# Screambooth.net
KiCad netlist of a schematic drawn in EAGLE
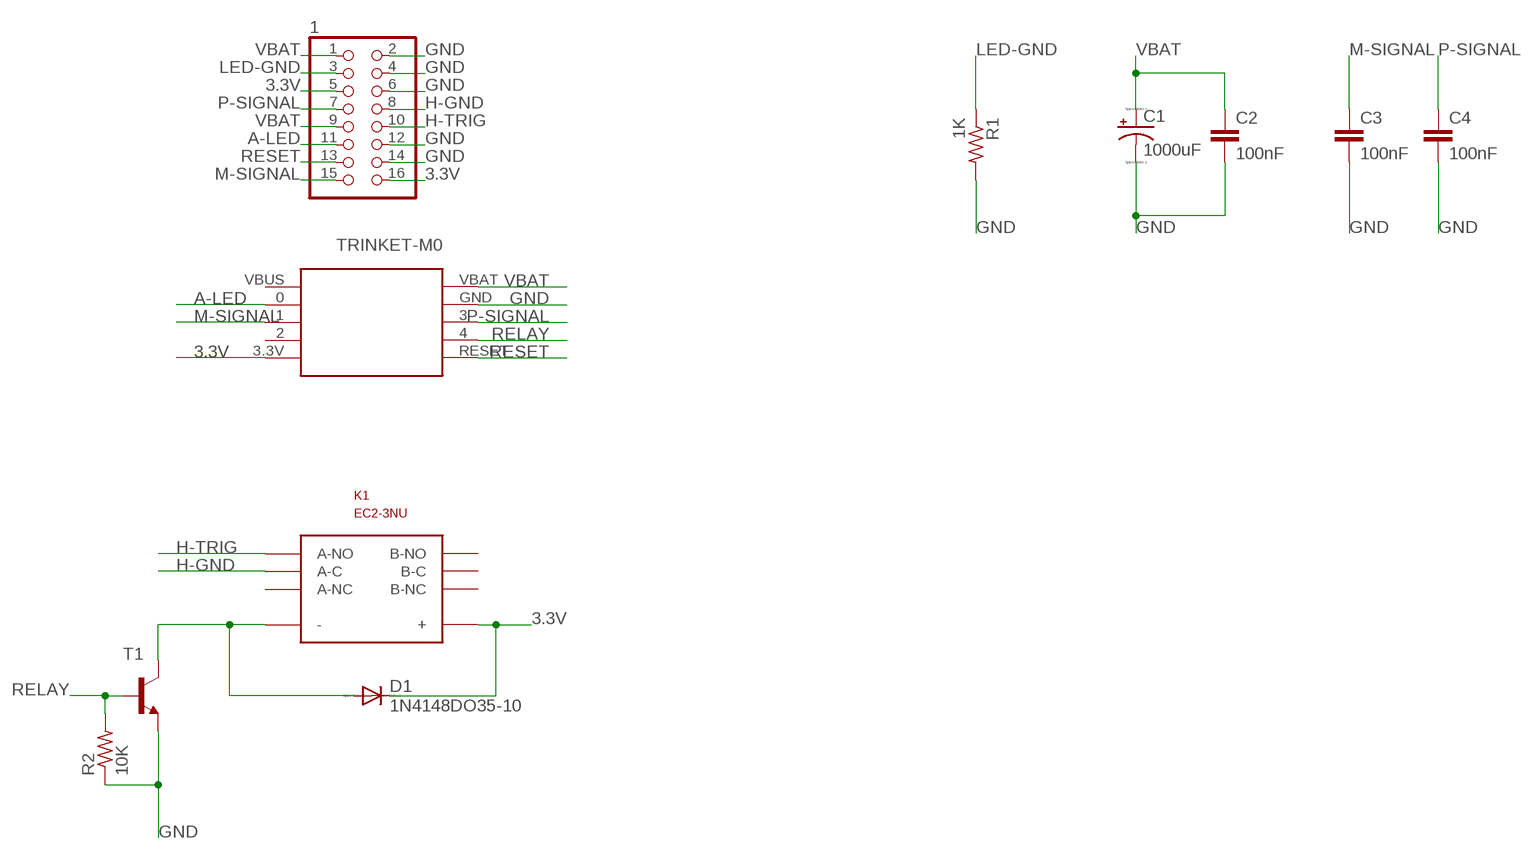
[diagram p0: schematic, sheet 1]

(export (version "E")
  (design (tool "Eeschema 10.0.6"))
  (components
    (comp (ref "1")
      (value "PINHD-2X8")
      (footprint "eagle-import:2X08")
      (libsource (lib "eagle-import") (part "PINHD-2X8"))
    )
    (comp (ref "C1")
      (value "1000uF")
      (footprint "eagle-import:E5-10,5")
      (libsource (lib "eagle-import") (part "CPOL-USE5-10.5"))
    )
    (comp (ref "C2")
      (value "100nF")
      (footprint "eagle-import:C050-030X075")
      (libsource (lib "eagle-import") (part "C-EU050-030X075"))
    )
    (comp (ref "C3")
      (value "100nF")
      (footprint "eagle-import:C050-030X075")
      (libsource (lib "eagle-import") (part "C-EU050-030X075"))
    )
    (comp (ref "C4")
      (value "100nF")
      (footprint "eagle-import:C050-030X075")
      (libsource (lib "eagle-import") (part "C-EU050-030X075"))
    )
    (comp (ref "D1")
      (value "1N4148DO35-10")
      (footprint "eagle-import:DO35-10")
      (libsource (lib "eagle-import") (part "1N4148DO35-10"))
    )
    (comp (ref "K1")
      (value "EC2-3NU")
      (footprint "eagle-import:EC2-RELAY")
      (libsource (lib "eagle-import") (part "EC2-3NU"))
    )
    (comp (ref "R1")
      (value "1K")
      (footprint "eagle-import:0207_10")
      (libsource (lib "eagle-import") (part "R-US_0207/10"))
    )
    (comp (ref "R2")
      (value "10K")
      (footprint "eagle-import:0207_10")
      (libsource (lib "eagle-import") (part "R-US_0207/10"))
    )
    (comp (ref "T1")
      (value "2N3904")
      (footprint "eagle-import:TO92")
      (libsource (lib "eagle-import") (part "2N3904"))
    )
    (comp (ref "TRINKET-M0")
      (value "TRINKET-M0")
      (footprint "eagle-import:TRINKET-M0")
      (libsource (lib "eagle-import") (part "TRINKET-M0"))
    )
  )
  (nets
    (net (code "1") (name "/3.3V") (class "Default")
      (node (ref "1") (pin "16") (pinfunction "16_16") (pintype "passive"))
      (node (ref "1") (pin "5") (pinfunction "5_5") (pintype "passive"))
      (node (ref "D1") (pin "C") (pinfunction "C_C") (pintype "passive"))
      (node (ref "K1") (pin "+") (pinfunction "+_+") (pintype "bidirectional"))
      (node (ref "TRINKET-M0") (pin "3.3V") (pinfunction "3.3V_3.3V") (pintype "bidirectional"))
    )
    (net (code "2") (name "/A-LED") (class "Default")
      (node (ref "1") (pin "11") (pinfunction "11_11") (pintype "passive"))
      (node (ref "TRINKET-M0") (pin "0") (pinfunction "0_0") (pintype "bidirectional"))
    )
    (net (code "3") (name "/GND") (class "Default")
      (node (ref "1") (pin "12") (pinfunction "12_12") (pintype "passive"))
      (node (ref "1") (pin "14") (pinfunction "14_14") (pintype "passive"))
      (node (ref "1") (pin "2") (pinfunction "2_2") (pintype "passive"))
      (node (ref "1") (pin "4") (pinfunction "4_4") (pintype "passive"))
      (node (ref "1") (pin "6") (pinfunction "6_6") (pintype "passive"))
      (node (ref "C1") (pin "-") (pinfunction "-_-") (pintype "passive"))
      (node (ref "C2") (pin "2") (pinfunction "2_2") (pintype "passive"))
      (node (ref "C3") (pin "2") (pinfunction "2_2") (pintype "passive"))
      (node (ref "C4") (pin "2") (pinfunction "2_2") (pintype "passive"))
      (node (ref "R1") (pin "2") (pinfunction "2_2") (pintype "passive"))
      (node (ref "R2") (pin "1") (pinfunction "1_1") (pintype "passive"))
      (node (ref "T1") (pin "3") (pinfunction "E_3") (pintype "passive"))
      (node (ref "TRINKET-M0") (pin "GND") (pinfunction "GND_GND") (pintype "bidirectional"))
    )
    (net (code "4") (name "/H-GND") (class "Default")
      (node (ref "1") (pin "8") (pinfunction "8_8") (pintype "passive"))
      (node (ref "K1") (pin "A-C") (pinfunction "A-C_A-C") (pintype "bidirectional"))
    )
    (net (code "5") (name "/H-TRIG") (class "Default")
      (node (ref "1") (pin "10") (pinfunction "10_10") (pintype "passive"))
      (node (ref "K1") (pin "A-NO") (pinfunction "A-NO_A-NO") (pintype "bidirectional"))
    )
    (net (code "6") (name "/LED-GND") (class "Default")
      (node (ref "1") (pin "3") (pinfunction "3_3") (pintype "passive"))
      (node (ref "R1") (pin "1") (pinfunction "1_1") (pintype "passive"))
    )
    (net (code "7") (name "/M-SIGNAL") (class "Default")
      (node (ref "1") (pin "15") (pinfunction "15_15") (pintype "passive"))
      (node (ref "C3") (pin "1") (pinfunction "1_1") (pintype "passive"))
      (node (ref "TRINKET-M0") (pin "1") (pinfunction "1_1") (pintype "bidirectional"))
    )
    (net (code "8") (name "/P-SIGNAL") (class "Default")
      (node (ref "1") (pin "7") (pinfunction "7_7") (pintype "passive"))
      (node (ref "C4") (pin "1") (pinfunction "1_1") (pintype "passive"))
      (node (ref "TRINKET-M0") (pin "3") (pinfunction "3_3") (pintype "bidirectional"))
    )
    (net (code "9") (name "/RELAY") (class "Default")
      (node (ref "R2") (pin "2") (pinfunction "2_2") (pintype "passive"))
      (node (ref "T1") (pin "2") (pinfunction "B_2") (pintype "passive"))
      (node (ref "TRINKET-M0") (pin "4") (pinfunction "4_4") (pintype "bidirectional"))
    )
    (net (code "10") (name "/RESET") (class "Default")
      (node (ref "1") (pin "13") (pinfunction "13_13") (pintype "passive"))
      (node (ref "TRINKET-M0") (pin "RESET") (pinfunction "RESET_RESET") (pintype "bidirectional"))
    )
    (net (code "11") (name "/VBAT") (class "Default")
      (node (ref "1") (pin "1") (pinfunction "1_1") (pintype "passive"))
      (node (ref "1") (pin "9") (pinfunction "9_9") (pintype "passive"))
      (node (ref "C1") (pin "+") (pinfunction "+_+") (pintype "passive"))
      (node (ref "C2") (pin "1") (pinfunction "1_1") (pintype "passive"))
      (node (ref "TRINKET-M0") (pin "VBAT") (pinfunction "VBAT_VBAT") (pintype "bidirectional"))
    )
    (net (code "12") (name "Net-(T1-C)") (class "Default")
      (node (ref "D1") (pin "A") (pinfunction "A_A") (pintype "passive"))
      (node (ref "K1") (pin "-") (pinfunction "-_-") (pintype "bidirectional"))
      (node (ref "T1") (pin "1") (pinfunction "C_1") (pintype "passive"))
    )
    (net (code "13") (name "unconnected-(K1-PadA-NC)") (class "Default")
      (node (ref "K1") (pin "A-NC") (pinfunction "A-NC_A-NC") (pintype "bidirectional"))
    )
    (net (code "14") (name "unconnected-(K1-PadB-C)") (class "Default")
      (node (ref "K1") (pin "B-C") (pinfunction "B-C_B-C") (pintype "bidirectional"))
    )
    (net (code "15") (name "unconnected-(K1-PadB-NC)") (class "Default")
      (node (ref "K1") (pin "B-NC") (pinfunction "B-NC_B-NC") (pintype "bidirectional"))
    )
    (net (code "16") (name "unconnected-(K1-PadB-NO)") (class "Default")
      (node (ref "K1") (pin "B-NO") (pinfunction "B-NO_B-NO") (pintype "bidirectional"))
    )
    (net (code "17") (name "unconnected-(TRINKET-M0-Pad2)") (class "Default")
      (node (ref "TRINKET-M0") (pin "2") (pinfunction "2_2") (pintype "bidirectional"))
    )
    (net (code "18") (name "unconnected-(TRINKET-M0-PadVBUS)") (class "Default")
      (node (ref "TRINKET-M0") (pin "VBUS") (pinfunction "VBUS_VBUS") (pintype "bidirectional"))
    )
  )
)
